# Parameter-Board.net
KiCad netlist of a schematic drawn in EAGLE
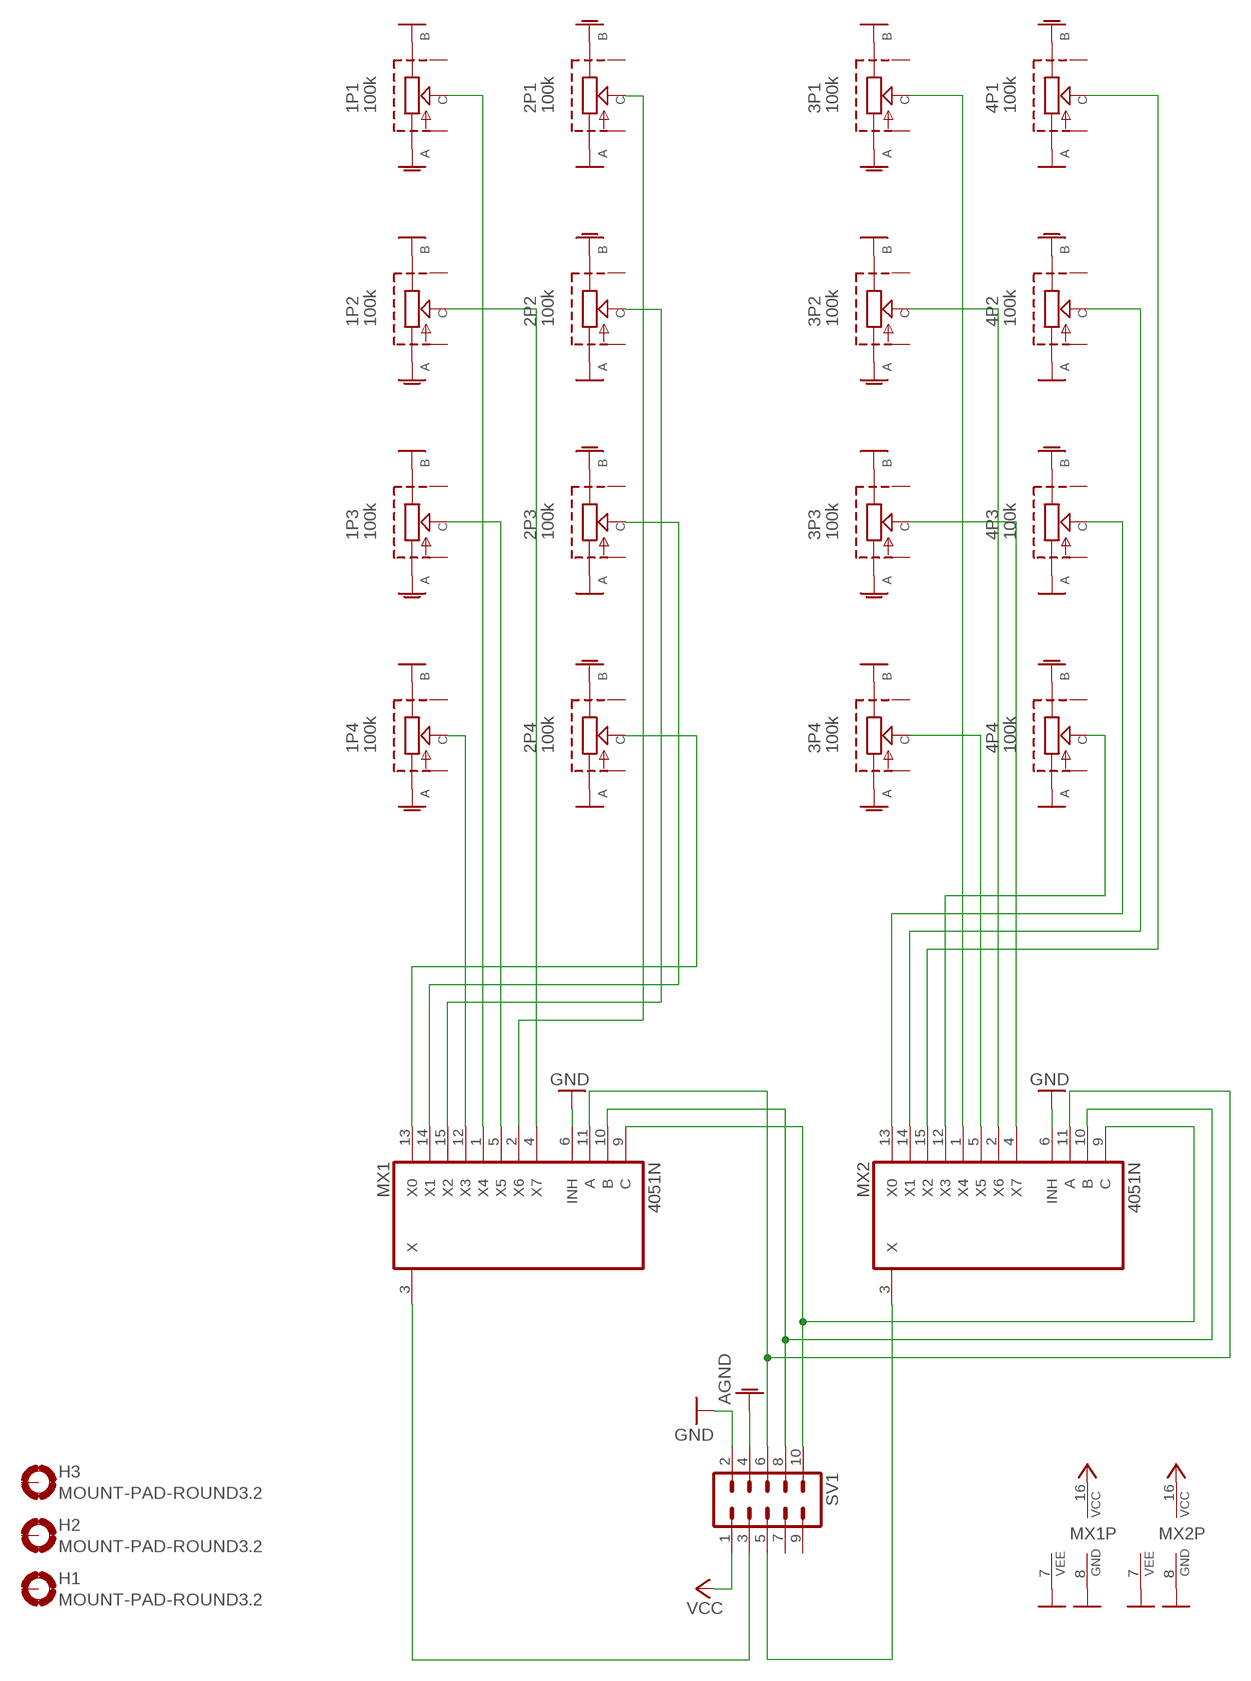
[diagram p0: schematic, sheet 1]

(export (version "E")
  (design (tool "Eeschema 10.0.6"))
  (components
    (comp (ref "1P1")
      (value "100k")
      (footprint "eagle-import:RK09K113")
      (libsource (lib "eagle-import") (part "RK09K113"))
    )
    (comp (ref "1P2")
      (value "100k")
      (footprint "eagle-import:RK09K113")
      (libsource (lib "eagle-import") (part "RK09K113"))
    )
    (comp (ref "1P3")
      (value "100k")
      (footprint "eagle-import:RK09K113")
      (libsource (lib "eagle-import") (part "RK09K113"))
    )
    (comp (ref "1P4")
      (value "100k")
      (footprint "eagle-import:RK09K113")
      (libsource (lib "eagle-import") (part "RK09K113"))
    )
    (comp (ref "2P1")
      (value "100k")
      (footprint "eagle-import:RK09K113")
      (libsource (lib "eagle-import") (part "RK09K113"))
    )
    (comp (ref "2P2")
      (value "100k")
      (footprint "eagle-import:RK09K113")
      (libsource (lib "eagle-import") (part "RK09K113"))
    )
    (comp (ref "2P3")
      (value "100k")
      (footprint "eagle-import:RK09K113")
      (libsource (lib "eagle-import") (part "RK09K113"))
    )
    (comp (ref "2P4")
      (value "100k")
      (footprint "eagle-import:RK09K113")
      (libsource (lib "eagle-import") (part "RK09K113"))
    )
    (comp (ref "3P1")
      (value "100k")
      (footprint "eagle-import:RK09K113")
      (libsource (lib "eagle-import") (part "RK09K113"))
    )
    (comp (ref "3P2")
      (value "100k")
      (footprint "eagle-import:RK09K113")
      (libsource (lib "eagle-import") (part "RK09K113"))
    )
    (comp (ref "3P3")
      (value "100k")
      (footprint "eagle-import:RK09K113")
      (libsource (lib "eagle-import") (part "RK09K113"))
    )
    (comp (ref "3P4")
      (value "100k")
      (footprint "eagle-import:RK09K113")
      (libsource (lib "eagle-import") (part "RK09K113"))
    )
    (comp (ref "4P1")
      (value "100k")
      (footprint "eagle-import:RK09K113")
      (libsource (lib "eagle-import") (part "RK09K113"))
    )
    (comp (ref "4P2")
      (value "100k")
      (footprint "eagle-import:RK09K113")
      (libsource (lib "eagle-import") (part "RK09K113"))
    )
    (comp (ref "4P3")
      (value "100k")
      (footprint "eagle-import:RK09K113")
      (libsource (lib "eagle-import") (part "RK09K113"))
    )
    (comp (ref "4P4")
      (value "100k")
      (footprint "eagle-import:RK09K113")
      (libsource (lib "eagle-import") (part "RK09K113"))
    )
    (comp (ref "H1")
      (value "MOUNT-PAD-ROUND3.2")
      (footprint "eagle-import:3,2-PAD")
      (libsource (lib "eagle-import") (part "MOUNT-PAD-ROUND3.2"))
    )
    (comp (ref "H2")
      (value "MOUNT-PAD-ROUND3.2")
      (footprint "eagle-import:3,2-PAD")
      (libsource (lib "eagle-import") (part "MOUNT-PAD-ROUND3.2"))
    )
    (comp (ref "H3")
      (value "MOUNT-PAD-ROUND3.2")
      (footprint "eagle-import:3,2-PAD")
      (libsource (lib "eagle-import") (part "MOUNT-PAD-ROUND3.2"))
    )
    (comp (ref "MX1")
      (value "4051N")
      (footprint "eagle-import:DIL16")
      (libsource (lib "eagle-import") (part "4051N"))
    )
    (comp (ref "MX2")
      (value "4051N")
      (footprint "eagle-import:DIL16")
      (libsource (lib "eagle-import") (part "4051N"))
    )
    (comp (ref "SV1")
      (value "ML10")
      (footprint "eagle-import:ML10")
      (libsource (lib "eagle-import") (part "ML10"))
    )
  )
  (nets
    (net (code "1") (name "AGND") (class "Default")
      (node (ref "1P1") (pin "A") (pinfunction "A_A") (pintype "passive"))
      (node (ref "1P2") (pin "A") (pinfunction "A_A") (pintype "passive"))
      (node (ref "1P3") (pin "A") (pinfunction "A_A") (pintype "passive"))
      (node (ref "1P4") (pin "A") (pinfunction "A_A") (pintype "passive"))
      (node (ref "2P1") (pin "B") (pinfunction "B_B") (pintype "passive"))
      (node (ref "2P2") (pin "B") (pinfunction "B_B") (pintype "passive"))
      (node (ref "2P3") (pin "B") (pinfunction "B_B") (pintype "passive"))
      (node (ref "2P4") (pin "B") (pinfunction "B_B") (pintype "passive"))
      (node (ref "3P1") (pin "A") (pinfunction "A_A") (pintype "passive"))
      (node (ref "3P2") (pin "A") (pinfunction "A_A") (pintype "passive"))
      (node (ref "3P3") (pin "A") (pinfunction "A_A") (pintype "passive"))
      (node (ref "3P4") (pin "A") (pinfunction "A_A") (pintype "passive"))
      (node (ref "4P1") (pin "B") (pinfunction "B_B") (pintype "passive"))
      (node (ref "4P2") (pin "B") (pinfunction "B_B") (pintype "passive"))
      (node (ref "4P3") (pin "B") (pinfunction "B_B") (pintype "passive"))
      (node (ref "4P4") (pin "B") (pinfunction "B_B") (pintype "passive"))
      (node (ref "SV1") (pin "4") (pinfunction "4_4") (pintype "passive"))
    )
    (net (code "2") (name "GND") (class "Default")
      (node (ref "1P1") (pin "B") (pinfunction "B_B") (pintype "passive"))
      (node (ref "1P2") (pin "B") (pinfunction "B_B") (pintype "passive"))
      (node (ref "1P3") (pin "B") (pinfunction "B_B") (pintype "passive"))
      (node (ref "1P4") (pin "B") (pinfunction "B_B") (pintype "passive"))
      (node (ref "2P1") (pin "A") (pinfunction "A_A") (pintype "passive"))
      (node (ref "2P2") (pin "A") (pinfunction "A_A") (pintype "passive"))
      (node (ref "2P3") (pin "A") (pinfunction "A_A") (pintype "passive"))
      (node (ref "2P4") (pin "A") (pinfunction "A_A") (pintype "passive"))
      (node (ref "3P1") (pin "B") (pinfunction "B_B") (pintype "passive"))
      (node (ref "3P2") (pin "B") (pinfunction "B_B") (pintype "passive"))
      (node (ref "3P3") (pin "B") (pinfunction "B_B") (pintype "passive"))
      (node (ref "3P4") (pin "B") (pinfunction "B_B") (pintype "passive"))
      (node (ref "4P1") (pin "A") (pinfunction "A_A") (pintype "passive"))
      (node (ref "4P2") (pin "A") (pinfunction "A_A") (pintype "passive"))
      (node (ref "4P3") (pin "A") (pinfunction "A_A") (pintype "passive"))
      (node (ref "4P4") (pin "A") (pinfunction "A_A") (pintype "passive"))
      (node (ref "MX1") (pin "6") (pinfunction "INH_6") (pintype "input"))
      (node (ref "MX1") (pin "7") (pinfunction "VEE_7") (pintype "power_in"))
      (node (ref "MX1") (pin "8") (pinfunction "GND_8") (pintype "power_in"))
      (node (ref "MX2") (pin "6") (pinfunction "INH_6") (pintype "input"))
      (node (ref "MX2") (pin "7") (pinfunction "VEE_7") (pintype "power_in"))
      (node (ref "MX2") (pin "8") (pinfunction "GND_8") (pintype "power_in"))
      (node (ref "SV1") (pin "2") (pinfunction "2_2") (pintype "passive"))
    )
    (net (code "3") (name "Net-(MX1A-A)") (class "Default")
      (node (ref "MX1") (pin "11") (pinfunction "A_11") (pintype "input"))
      (node (ref "MX2") (pin "11") (pinfunction "A_11") (pintype "input"))
      (node (ref "SV1") (pin "6") (pinfunction "6_6") (pintype "passive"))
    )
    (net (code "4") (name "Net-(MX1A-B)") (class "Default")
      (node (ref "MX1") (pin "10") (pinfunction "B_10") (pintype "input"))
      (node (ref "MX2") (pin "10") (pinfunction "B_10") (pintype "input"))
      (node (ref "SV1") (pin "8") (pinfunction "8_8") (pintype "passive"))
    )
    (net (code "5") (name "Net-(MX1A-C)") (class "Default")
      (node (ref "MX1") (pin "9") (pinfunction "C_9") (pintype "input"))
      (node (ref "MX2") (pin "9") (pinfunction "C_9") (pintype "input"))
      (node (ref "SV1") (pin "10") (pinfunction "10_10") (pintype "passive"))
    )
    (net (code "6") (name "Net-(MX1A-X)") (class "Default")
      (node (ref "MX1") (pin "3") (pinfunction "X_3") (pintype "bidirectional"))
      (node (ref "SV1") (pin "3") (pinfunction "3_3") (pintype "passive"))
    )
    (net (code "7") (name "Net-(MX1A-X0)") (class "Default")
      (node (ref "2P4") (pin "C") (pinfunction "C_C") (pintype "passive"))
      (node (ref "MX1") (pin "13") (pinfunction "X0_13") (pintype "bidirectional"))
    )
    (net (code "8") (name "Net-(MX1A-X1)") (class "Default")
      (node (ref "2P3") (pin "C") (pinfunction "C_C") (pintype "passive"))
      (node (ref "MX1") (pin "14") (pinfunction "X1_14") (pintype "bidirectional"))
    )
    (net (code "9") (name "Net-(MX1A-X2)") (class "Default")
      (node (ref "2P2") (pin "C") (pinfunction "C_C") (pintype "passive"))
      (node (ref "MX1") (pin "15") (pinfunction "X2_15") (pintype "bidirectional"))
    )
    (net (code "10") (name "Net-(MX1A-X3)") (class "Default")
      (node (ref "1P4") (pin "C") (pinfunction "C_C") (pintype "passive"))
      (node (ref "MX1") (pin "12") (pinfunction "X3_12") (pintype "bidirectional"))
    )
    (net (code "11") (name "Net-(MX1A-X4)") (class "Default")
      (node (ref "1P1") (pin "C") (pinfunction "C_C") (pintype "passive"))
      (node (ref "MX1") (pin "1") (pinfunction "X4_1") (pintype "bidirectional"))
    )
    (net (code "12") (name "Net-(MX1A-X5)") (class "Default")
      (node (ref "1P3") (pin "C") (pinfunction "C_C") (pintype "passive"))
      (node (ref "MX1") (pin "5") (pinfunction "X5_5") (pintype "bidirectional"))
    )
    (net (code "13") (name "Net-(MX1A-X6)") (class "Default")
      (node (ref "2P1") (pin "C") (pinfunction "C_C") (pintype "passive"))
      (node (ref "MX1") (pin "2") (pinfunction "X6_2") (pintype "bidirectional"))
    )
    (net (code "14") (name "Net-(MX1A-X7)") (class "Default")
      (node (ref "1P2") (pin "C") (pinfunction "C_C") (pintype "passive"))
      (node (ref "MX1") (pin "4") (pinfunction "X7_4") (pintype "bidirectional"))
    )
    (net (code "15") (name "Net-(MX2A-X)") (class "Default")
      (node (ref "MX2") (pin "3") (pinfunction "X_3") (pintype "bidirectional"))
      (node (ref "SV1") (pin "5") (pinfunction "5_5") (pintype "passive"))
    )
    (net (code "16") (name "Net-(MX2A-X0)") (class "Default")
      (node (ref "4P3") (pin "C") (pinfunction "C_C") (pintype "passive"))
      (node (ref "MX2") (pin "13") (pinfunction "X0_13") (pintype "bidirectional"))
    )
    (net (code "17") (name "Net-(MX2A-X1)") (class "Default")
      (node (ref "4P2") (pin "C") (pinfunction "C_C") (pintype "passive"))
      (node (ref "MX2") (pin "14") (pinfunction "X1_14") (pintype "bidirectional"))
    )
    (net (code "18") (name "Net-(MX2A-X2)") (class "Default")
      (node (ref "4P1") (pin "C") (pinfunction "C_C") (pintype "passive"))
      (node (ref "MX2") (pin "15") (pinfunction "X2_15") (pintype "bidirectional"))
    )
    (net (code "19") (name "Net-(MX2A-X3)") (class "Default")
      (node (ref "4P4") (pin "C") (pinfunction "C_C") (pintype "passive"))
      (node (ref "MX2") (pin "12") (pinfunction "X3_12") (pintype "bidirectional"))
    )
    (net (code "20") (name "Net-(MX2A-X4)") (class "Default")
      (node (ref "3P1") (pin "C") (pinfunction "C_C") (pintype "passive"))
      (node (ref "MX2") (pin "1") (pinfunction "X4_1") (pintype "bidirectional"))
    )
    (net (code "21") (name "Net-(MX2A-X5)") (class "Default")
      (node (ref "3P4") (pin "C") (pinfunction "C_C") (pintype "passive"))
      (node (ref "MX2") (pin "5") (pinfunction "X5_5") (pintype "bidirectional"))
    )
    (net (code "22") (name "Net-(MX2A-X6)") (class "Default")
      (node (ref "3P2") (pin "C") (pinfunction "C_C") (pintype "passive"))
      (node (ref "MX2") (pin "2") (pinfunction "X6_2") (pintype "bidirectional"))
    )
    (net (code "23") (name "Net-(MX2A-X7)") (class "Default")
      (node (ref "3P3") (pin "C") (pinfunction "C_C") (pintype "passive"))
      (node (ref "MX2") (pin "4") (pinfunction "X7_4") (pintype "bidirectional"))
    )
    (net (code "24") (name "VCC") (class "Default")
      (node (ref "MX1") (pin "16") (pinfunction "VCC_16") (pintype "power_in"))
      (node (ref "MX2") (pin "16") (pinfunction "VCC_16") (pintype "power_in"))
      (node (ref "SV1") (pin "1") (pinfunction "1_1") (pintype "passive"))
    )
    (net (code "25") (name "unconnected-(1P1-PadCASE1)") (class "Default")
      (node (ref "1P1") (pin "CASE1") (pinfunction "CASE1_CASE1") (pintype "passive"))
    )
    (net (code "26") (name "unconnected-(1P1-PadCASE2)") (class "Default")
      (node (ref "1P1") (pin "CASE2") (pinfunction "CASE2_CASE2") (pintype "passive"))
    )
    (net (code "27") (name "unconnected-(1P2-PadCASE1)") (class "Default")
      (node (ref "1P2") (pin "CASE1") (pinfunction "CASE1_CASE1") (pintype "passive"))
    )
    (net (code "28") (name "unconnected-(1P2-PadCASE2)") (class "Default")
      (node (ref "1P2") (pin "CASE2") (pinfunction "CASE2_CASE2") (pintype "passive"))
    )
    (net (code "29") (name "unconnected-(1P3-PadCASE1)") (class "Default")
      (node (ref "1P3") (pin "CASE1") (pinfunction "CASE1_CASE1") (pintype "passive"))
    )
    (net (code "30") (name "unconnected-(1P3-PadCASE2)") (class "Default")
      (node (ref "1P3") (pin "CASE2") (pinfunction "CASE2_CASE2") (pintype "passive"))
    )
    (net (code "31") (name "unconnected-(1P4-PadCASE1)") (class "Default")
      (node (ref "1P4") (pin "CASE1") (pinfunction "CASE1_CASE1") (pintype "passive"))
    )
    (net (code "32") (name "unconnected-(1P4-PadCASE2)") (class "Default")
      (node (ref "1P4") (pin "CASE2") (pinfunction "CASE2_CASE2") (pintype "passive"))
    )
    (net (code "33") (name "unconnected-(2P1-PadCASE1)") (class "Default")
      (node (ref "2P1") (pin "CASE1") (pinfunction "CASE1_CASE1") (pintype "passive"))
    )
    (net (code "34") (name "unconnected-(2P1-PadCASE2)") (class "Default")
      (node (ref "2P1") (pin "CASE2") (pinfunction "CASE2_CASE2") (pintype "passive"))
    )
    (net (code "35") (name "unconnected-(2P2-PadCASE1)") (class "Default")
      (node (ref "2P2") (pin "CASE1") (pinfunction "CASE1_CASE1") (pintype "passive"))
    )
    (net (code "36") (name "unconnected-(2P2-PadCASE2)") (class "Default")
      (node (ref "2P2") (pin "CASE2") (pinfunction "CASE2_CASE2") (pintype "passive"))
    )
    (net (code "37") (name "unconnected-(2P3-PadCASE1)") (class "Default")
      (node (ref "2P3") (pin "CASE1") (pinfunction "CASE1_CASE1") (pintype "passive"))
    )
    (net (code "38") (name "unconnected-(2P3-PadCASE2)") (class "Default")
      (node (ref "2P3") (pin "CASE2") (pinfunction "CASE2_CASE2") (pintype "passive"))
    )
    (net (code "39") (name "unconnected-(2P4-PadCASE1)") (class "Default")
      (node (ref "2P4") (pin "CASE1") (pinfunction "CASE1_CASE1") (pintype "passive"))
    )
    (net (code "40") (name "unconnected-(2P4-PadCASE2)") (class "Default")
      (node (ref "2P4") (pin "CASE2") (pinfunction "CASE2_CASE2") (pintype "passive"))
    )
    (net (code "41") (name "unconnected-(3P1-PadCASE1)") (class "Default")
      (node (ref "3P1") (pin "CASE1") (pinfunction "CASE1_CASE1") (pintype "passive"))
    )
    (net (code "42") (name "unconnected-(3P1-PadCASE2)") (class "Default")
      (node (ref "3P1") (pin "CASE2") (pinfunction "CASE2_CASE2") (pintype "passive"))
    )
    (net (code "43") (name "unconnected-(3P2-PadCASE1)") (class "Default")
      (node (ref "3P2") (pin "CASE1") (pinfunction "CASE1_CASE1") (pintype "passive"))
    )
    (net (code "44") (name "unconnected-(3P2-PadCASE2)") (class "Default")
      (node (ref "3P2") (pin "CASE2") (pinfunction "CASE2_CASE2") (pintype "passive"))
    )
    (net (code "45") (name "unconnected-(3P3-PadCASE1)") (class "Default")
      (node (ref "3P3") (pin "CASE1") (pinfunction "CASE1_CASE1") (pintype "passive"))
    )
    (net (code "46") (name "unconnected-(3P3-PadCASE2)") (class "Default")
      (node (ref "3P3") (pin "CASE2") (pinfunction "CASE2_CASE2") (pintype "passive"))
    )
    (net (code "47") (name "unconnected-(3P4-PadCASE1)") (class "Default")
      (node (ref "3P4") (pin "CASE1") (pinfunction "CASE1_CASE1") (pintype "passive"))
    )
    (net (code "48") (name "unconnected-(3P4-PadCASE2)") (class "Default")
      (node (ref "3P4") (pin "CASE2") (pinfunction "CASE2_CASE2") (pintype "passive"))
    )
    (net (code "49") (name "unconnected-(4P1-PadCASE1)") (class "Default")
      (node (ref "4P1") (pin "CASE1") (pinfunction "CASE1_CASE1") (pintype "passive"))
    )
    (net (code "50") (name "unconnected-(4P1-PadCASE2)") (class "Default")
      (node (ref "4P1") (pin "CASE2") (pinfunction "CASE2_CASE2") (pintype "passive"))
    )
    (net (code "51") (name "unconnected-(4P2-PadCASE1)") (class "Default")
      (node (ref "4P2") (pin "CASE1") (pinfunction "CASE1_CASE1") (pintype "passive"))
    )
    (net (code "52") (name "unconnected-(4P2-PadCASE2)") (class "Default")
      (node (ref "4P2") (pin "CASE2") (pinfunction "CASE2_CASE2") (pintype "passive"))
    )
    (net (code "53") (name "unconnected-(4P3-PadCASE1)") (class "Default")
      (node (ref "4P3") (pin "CASE1") (pinfunction "CASE1_CASE1") (pintype "passive"))
    )
    (net (code "54") (name "unconnected-(4P3-PadCASE2)") (class "Default")
      (node (ref "4P3") (pin "CASE2") (pinfunction "CASE2_CASE2") (pintype "passive"))
    )
    (net (code "55") (name "unconnected-(4P4-PadCASE1)") (class "Default")
      (node (ref "4P4") (pin "CASE1") (pinfunction "CASE1_CASE1") (pintype "passive"))
    )
    (net (code "56") (name "unconnected-(4P4-PadCASE2)") (class "Default")
      (node (ref "4P4") (pin "CASE2") (pinfunction "CASE2_CASE2") (pintype "passive"))
    )
    (net (code "57") (name "unconnected-(H1-MOUNT-PadB3,2)") (class "Default")
      (node (ref "H1") (pin "B3,2") (pinfunction "MOUNT_B3,2") (pintype "passive"))
    )
    (net (code "58") (name "unconnected-(H2-MOUNT-PadB3,2)") (class "Default")
      (node (ref "H2") (pin "B3,2") (pinfunction "MOUNT_B3,2") (pintype "passive"))
    )
    (net (code "59") (name "unconnected-(H3-MOUNT-PadB3,2)") (class "Default")
      (node (ref "H3") (pin "B3,2") (pinfunction "MOUNT_B3,2") (pintype "passive"))
    )
    (net (code "60") (name "unconnected-(SV1-Pad7)") (class "Default")
      (node (ref "SV1") (pin "7") (pinfunction "7_7") (pintype "passive"))
    )
    (net (code "61") (name "unconnected-(SV1-Pad9)") (class "Default")
      (node (ref "SV1") (pin "9") (pinfunction "9_9") (pintype "passive"))
    )
  )
)
